# regulation-level-shifter-mk-1_3.net
KiCad netlist of a schematic drawn in EAGLE
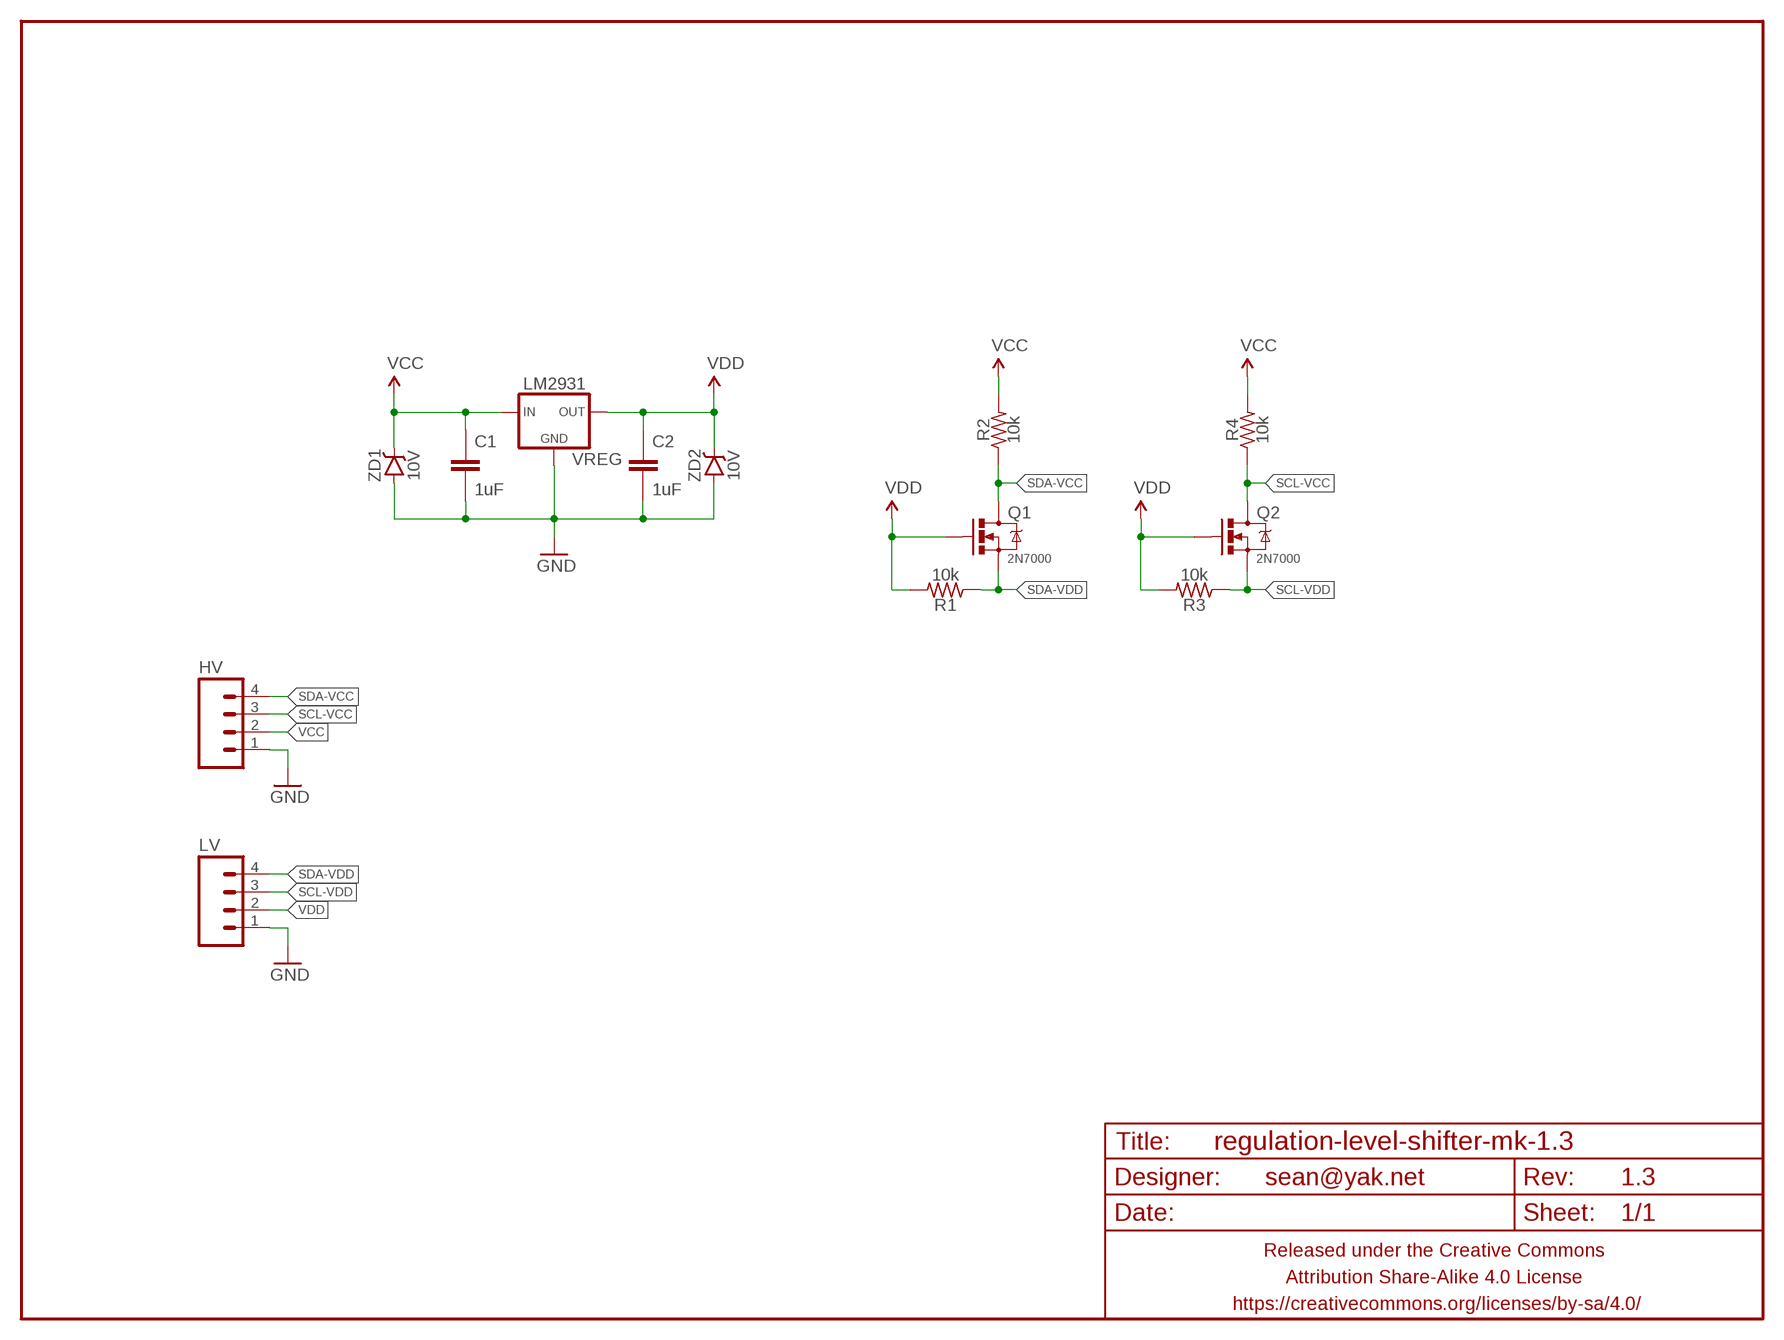
[diagram p0: schematic, sheet 1]

(export (version "E")
  (design (tool "Eeschema 10.0.6"))
  (components
    (comp (ref "C1")
      (value "1uF")
      (footprint "eagle-import:C025-024X044")
      (libsource (lib "eagle-import") (part "CAPACITOR-CERAMIC025-024X044"))
    )
    (comp (ref "C2")
      (value "1uF")
      (footprint "eagle-import:C025-024X044")
      (libsource (lib "eagle-import") (part "CAPACITOR-CERAMIC025-024X044"))
    )
    (comp (ref "FRAME1")
      (value "FRAME-LETTERNO_PACKAGE")
      (footprint "eagle-import:DUMMY")
      (fields (field (name "DESIGNER") "sean@yak.net") (field (name "VERSION") "1.3"))
      (libsource (lib "eagle-import") (part "FRAME-LETTERNO_PACKAGE"))
    )
    (comp (ref "HV")
      (value "M04PTH")
      (footprint "eagle-import:1X04-PTH-VERT")
      (libsource (lib "eagle-import") (part "M04PTH"))
    )
    (comp (ref "LV")
      (value "M04PTH")
      (footprint "eagle-import:1X04-PTH-VERT")
      (libsource (lib "eagle-import") (part "M04PTH"))
    )
    (comp (ref "Q1")
      (value "2N7000")
      (footprint "eagle-import:TO-92-AMMO")
      (libsource (lib "eagle-import") (part "MOSFET-NCHANNEL2N7000-AMMO"))
    )
    (comp (ref "Q2")
      (value "2N7000")
      (footprint "eagle-import:TO-92-AMMO")
      (libsource (lib "eagle-import") (part "MOSFET-NCHANNEL2N7000-AMMO"))
    )
    (comp (ref "R1")
      (value "10k")
      (footprint "eagle-import:RESISTOR-AXIAL-PTH-5.08MM")
      (libsource (lib "eagle-import") (part "RESISTORPTH-AXIAL-5.08MM"))
    )
    (comp (ref "R2")
      (value "10k")
      (footprint "eagle-import:RESISTOR-AXIAL-PTH-5.08MM")
      (libsource (lib "eagle-import") (part "RESISTORPTH-AXIAL-5.08MM"))
    )
    (comp (ref "R3")
      (value "10k")
      (footprint "eagle-import:RESISTOR-AXIAL-PTH-5.08MM")
      (libsource (lib "eagle-import") (part "RESISTORPTH-AXIAL-5.08MM"))
    )
    (comp (ref "R4")
      (value "10k")
      (footprint "eagle-import:RESISTOR-AXIAL-PTH-5.08MM")
      (libsource (lib "eagle-import") (part "RESISTORPTH-AXIAL-5.08MM"))
    )
    (comp (ref "VREG")
      (value "LM2931")
      (footprint "eagle-import:TO-92-AMMO")
      (libsource (lib "eagle-import") (part "V_REG_78XXTO-92-INLINE"))
    )
    (comp (ref "ZD1")
      (value "10V")
      (footprint "eagle-import:DIODE-ZENNER-7.62MM")
      (libsource (lib "eagle-import") (part "DIODE-ZENER7.62MM-PTH"))
    )
    (comp (ref "ZD2")
      (value "10V")
      (footprint "eagle-import:DIODE-ZENNER-7.62MM")
      (libsource (lib "eagle-import") (part "DIODE-ZENER7.62MM-PTH"))
    )
  )
  (nets
    (net (code "1") (name "GND") (class "Default")
      (node (ref "C1") (pin "2") (pinfunction "2_2") (pintype "passive"))
      (node (ref "C2") (pin "2") (pinfunction "2_2") (pintype "passive"))
      (node (ref "HV") (pin "1") (pinfunction "1_1") (pintype "passive"))
      (node (ref "LV") (pin "1") (pinfunction "1_1") (pintype "passive"))
      (node (ref "VREG") (pin "2") (pinfunction "GND_2") (pintype "bidirectional"))
      (node (ref "ZD1") (pin "A") (pinfunction "A_A") (pintype "passive"))
      (node (ref "ZD2") (pin "A") (pinfunction "A_A") (pintype "passive"))
    )
    (net (code "2") (name "SCL-VCC") (class "Default")
      (node (ref "HV") (pin "3") (pinfunction "3_3") (pintype "passive"))
      (node (ref "Q2") (pin "3") (pinfunction "D_3") (pintype "passive"))
      (node (ref "R4") (pin "P$1") (pinfunction "1_P$1") (pintype "passive"))
    )
    (net (code "3") (name "SCL-VDD") (class "Default")
      (node (ref "LV") (pin "3") (pinfunction "3_3") (pintype "passive"))
      (node (ref "Q2") (pin "1") (pinfunction "S_1") (pintype "passive"))
      (node (ref "R3") (pin "P$1") (pinfunction "1_P$1") (pintype "passive"))
    )
    (net (code "4") (name "SDA-VCC") (class "Default")
      (node (ref "HV") (pin "4") (pinfunction "4_4") (pintype "passive"))
      (node (ref "Q1") (pin "3") (pinfunction "D_3") (pintype "passive"))
      (node (ref "R2") (pin "P$1") (pinfunction "1_P$1") (pintype "passive"))
    )
    (net (code "5") (name "SDA-VDD") (class "Default")
      (node (ref "LV") (pin "4") (pinfunction "4_4") (pintype "passive"))
      (node (ref "Q1") (pin "1") (pinfunction "S_1") (pintype "passive"))
      (node (ref "R1") (pin "P$1") (pinfunction "1_P$1") (pintype "passive"))
    )
    (net (code "6") (name "VCC") (class "Default")
      (node (ref "C1") (pin "1") (pinfunction "1_1") (pintype "passive"))
      (node (ref "HV") (pin "2") (pinfunction "2_2") (pintype "passive"))
      (node (ref "R2") (pin "P$2") (pinfunction "2_P$2") (pintype "passive"))
      (node (ref "R4") (pin "P$2") (pinfunction "2_P$2") (pintype "passive"))
      (node (ref "VREG") (pin "1") (pinfunction "IN_1") (pintype "bidirectional"))
      (node (ref "ZD1") (pin "K") (pinfunction "C_K") (pintype "passive"))
    )
    (net (code "7") (name "VDD") (class "Default")
      (node (ref "C2") (pin "1") (pinfunction "1_1") (pintype "passive"))
      (node (ref "LV") (pin "2") (pinfunction "2_2") (pintype "passive"))
      (node (ref "Q1") (pin "2") (pinfunction "G_2") (pintype "passive"))
      (node (ref "Q2") (pin "2") (pinfunction "G_2") (pintype "passive"))
      (node (ref "R1") (pin "P$2") (pinfunction "2_P$2") (pintype "passive"))
      (node (ref "R3") (pin "P$2") (pinfunction "2_P$2") (pintype "passive"))
      (node (ref "VREG") (pin "3") (pinfunction "OUT_3") (pintype "bidirectional"))
      (node (ref "ZD2") (pin "K") (pinfunction "C_K") (pintype "passive"))
    )
  )
)
